# usb_hub.net
KiCad netlist of a schematic drawn in EAGLE
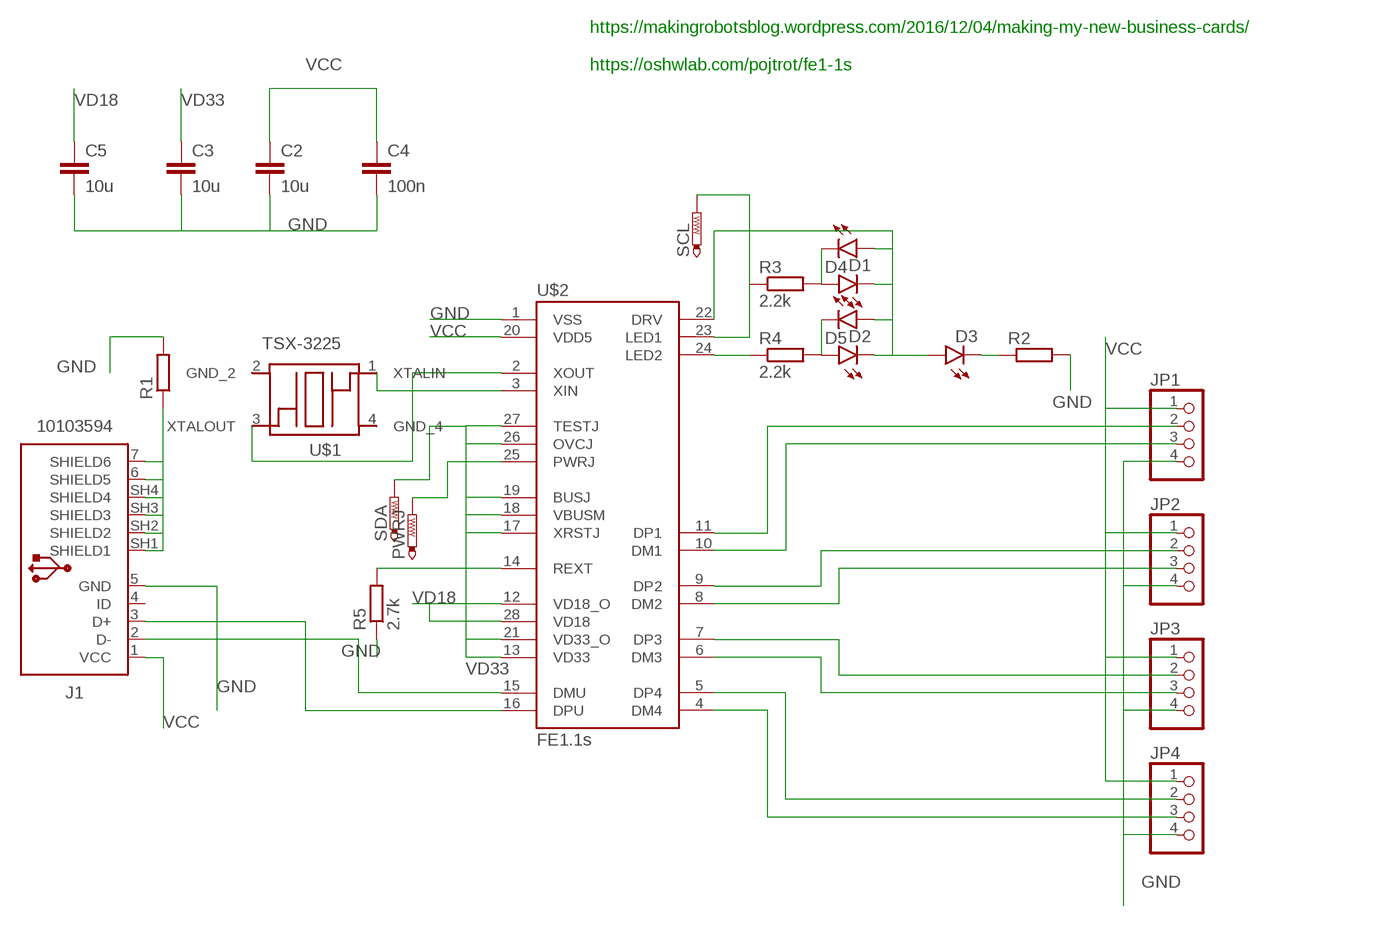
[diagram p0: schematic, sheet 1]

(export (version "E")
  (design (tool "Eeschema 10.0.6"))
  (components
    (comp (ref "C2")
      (value "10u")
      (footprint "eagle-import:C0805")
      (libsource (lib "eagle-import") (part "C-EUC0805"))
    )
    (comp (ref "C3")
      (value "10u")
      (footprint "eagle-import:C0805")
      (libsource (lib "eagle-import") (part "C-EUC0805"))
    )
    (comp (ref "C4")
      (value "100n")
      (footprint "eagle-import:C0603")
      (libsource (lib "eagle-import") (part "C-EUC0603"))
    )
    (comp (ref "C5")
      (value "10u")
      (footprint "eagle-import:C0805")
      (libsource (lib "eagle-import") (part "C-EUC0805"))
    )
    (comp (ref "D1")
      (value "LEDCHIP-LED0603")
      (footprint "eagle-import:CHIP-LED0603")
      (libsource (lib "eagle-import") (part "LEDCHIP-LED0603"))
    )
    (comp (ref "D2")
      (value "LEDCHIP-LED0603")
      (footprint "eagle-import:CHIP-LED0603")
      (libsource (lib "eagle-import") (part "LEDCHIP-LED0603"))
    )
    (comp (ref "D3")
      (value "LEDCHIP-LED0603")
      (footprint "eagle-import:CHIP-LED0603")
      (libsource (lib "eagle-import") (part "LEDCHIP-LED0603"))
    )
    (comp (ref "D4")
      (value "LEDCHIP-LED0603")
      (footprint "eagle-import:CHIP-LED0603")
      (libsource (lib "eagle-import") (part "LEDCHIP-LED0603"))
    )
    (comp (ref "D5")
      (value "LEDCHIP-LED0603")
      (footprint "eagle-import:CHIP-LED0603")
      (libsource (lib "eagle-import") (part "LEDCHIP-LED0603"))
    )
    (comp (ref "J1")
      (value "10103594")
      (footprint "eagle-import:10103594")
      (fields (field (name "MANUFACTURER") "Amphenol ICC (FCI)") (field (name "MPN") "10103594-0001LF"))
      (libsource (lib "eagle-import") (part "10103594"))
    )
    (comp (ref "JP1")
      (value "PINHD-1X4")
      (footprint "eagle-import:1X04")
      (libsource (lib "eagle-import") (part "PINHD-1X4"))
    )
    (comp (ref "JP2")
      (value "PINHD-1X4")
      (footprint "eagle-import:1X04")
      (libsource (lib "eagle-import") (part "PINHD-1X4"))
    )
    (comp (ref "JP3")
      (value "PINHD-1X4")
      (footprint "eagle-import:1X04")
      (libsource (lib "eagle-import") (part "PINHD-1X4"))
    )
    (comp (ref "JP4")
      (value "PINHD-1X4")
      (footprint "eagle-import:1X04")
      (libsource (lib "eagle-import") (part "PINHD-1X4"))
    )
    (comp (ref "PWRJ")
      (value "PTR1B1,27")
      (footprint "eagle-import:B1,27")
      (libsource (lib "eagle-import") (part "PTR1B1,27"))
    )
    (comp (ref "R1")
      (value "R-EU_R0603")
      (footprint "eagle-import:R0603")
      (libsource (lib "eagle-import") (part "R-EU_R0603"))
    )
    (comp (ref "R2")
      (value "R-EU_R0603")
      (footprint "eagle-import:R0603")
      (libsource (lib "eagle-import") (part "R-EU_R0603"))
    )
    (comp (ref "R3")
      (value "2.2k")
      (footprint "eagle-import:R0603")
      (libsource (lib "eagle-import") (part "R-EU_R0603"))
    )
    (comp (ref "R4")
      (value "2.2k")
      (footprint "eagle-import:R0603")
      (libsource (lib "eagle-import") (part "R-EU_R0603"))
    )
    (comp (ref "R5")
      (value "2.7k")
      (footprint "eagle-import:R0603")
      (libsource (lib "eagle-import") (part "R-EU_R0603"))
    )
    (comp (ref "SCL")
      (value "PTR1B1,27")
      (footprint "eagle-import:B1,27")
      (libsource (lib "eagle-import") (part "PTR1B1,27"))
    )
    (comp (ref "SDA")
      (value "PTR1B1,27")
      (footprint "eagle-import:B1,27")
      (libsource (lib "eagle-import") (part "PTR1B1,27"))
    )
    (comp (ref "U$1")
      (value "TSX-3225")
      (footprint "eagle-import:TSX-3225")
      (libsource (lib "eagle-import") (part "TSX-3225"))
    )
    (comp (ref "U$2")
      (value "FE1.1S")
      (footprint "eagle-import:FE1.1S_SSOP-28")
      (libsource (lib "eagle-import") (part "FE1.1S"))
    )
  )
  (nets
    (net (code "1") (name "/GND") (class "Default")
      (node (ref "C2") (pin "2") (pinfunction "2_2") (pintype "passive"))
      (node (ref "C3") (pin "2") (pinfunction "2_2") (pintype "passive"))
      (node (ref "C4") (pin "2") (pinfunction "2_2") (pintype "passive"))
      (node (ref "C5") (pin "2") (pinfunction "2_2") (pintype "passive"))
      (node (ref "J1") (pin "5") (pinfunction "GND_5") (pintype "power_in"))
      (node (ref "JP1") (pin "4") (pinfunction "4_4") (pintype "passive"))
      (node (ref "JP2") (pin "4") (pinfunction "4_4") (pintype "passive"))
      (node (ref "JP3") (pin "4") (pinfunction "4_4") (pintype "passive"))
      (node (ref "JP4") (pin "4") (pinfunction "4_4") (pintype "passive"))
      (node (ref "R1") (pin "2") (pinfunction "2_2") (pintype "passive"))
      (node (ref "R2") (pin "2") (pinfunction "2_2") (pintype "passive"))
      (node (ref "R5") (pin "1") (pinfunction "1_1") (pintype "passive"))
      (node (ref "U$2") (pin "1") (pinfunction "VSS_1") (pintype "bidirectional"))
    )
    (net (code "2") (name "/VCC") (class "Default")
      (node (ref "C2") (pin "1") (pinfunction "1_1") (pintype "passive"))
      (node (ref "C4") (pin "1") (pinfunction "1_1") (pintype "passive"))
      (node (ref "J1") (pin "1") (pinfunction "VCC_1") (pintype "power_in"))
      (node (ref "JP1") (pin "1") (pinfunction "1_1") (pintype "passive"))
      (node (ref "JP2") (pin "1") (pinfunction "1_1") (pintype "passive"))
      (node (ref "JP3") (pin "1") (pinfunction "1_1") (pintype "passive"))
      (node (ref "JP4") (pin "1") (pinfunction "1_1") (pintype "passive"))
      (node (ref "U$2") (pin "20") (pinfunction "VDD5_20") (pintype "bidirectional"))
    )
    (net (code "3") (name "/VD18") (class "Default")
      (node (ref "C5") (pin "1") (pinfunction "1_1") (pintype "passive"))
      (node (ref "U$2") (pin "12") (pinfunction "VD18_O_12") (pintype "bidirectional"))
      (node (ref "U$2") (pin "28") (pinfunction "VD18_28") (pintype "bidirectional"))
    )
    (net (code "4") (name "/VD33") (class "Default")
      (node (ref "C3") (pin "1") (pinfunction "1_1") (pintype "passive"))
      (node (ref "SDA") (pin "TP") (pinfunction "TP_TP") (pintype "input"))
      (node (ref "U$2") (pin "13") (pinfunction "VD33_13") (pintype "bidirectional"))
      (node (ref "U$2") (pin "17") (pinfunction "XRSTJ_17") (pintype "bidirectional"))
      (node (ref "U$2") (pin "18") (pinfunction "VBUSM_18") (pintype "bidirectional"))
      (node (ref "U$2") (pin "19") (pinfunction "BUSJ_19") (pintype "bidirectional"))
      (node (ref "U$2") (pin "21") (pinfunction "VD33_O_21") (pintype "bidirectional"))
      (node (ref "U$2") (pin "26") (pinfunction "OVCJ_26") (pintype "bidirectional"))
      (node (ref "U$2") (pin "27") (pinfunction "TESTJ_27") (pintype "bidirectional"))
    )
    (net (code "5") (name "Net-(D1-PadA)") (class "Default")
      (node (ref "D1") (pin "A") (pinfunction "A_A") (pintype "passive"))
      (node (ref "D4") (pin "C") (pinfunction "C_C") (pintype "passive"))
      (node (ref "R3") (pin "2") (pinfunction "2_2") (pintype "passive"))
    )
    (net (code "6") (name "Net-(D2-PadA)") (class "Default")
      (node (ref "D2") (pin "A") (pinfunction "A_A") (pintype "passive"))
      (node (ref "D5") (pin "C") (pinfunction "C_C") (pintype "passive"))
      (node (ref "R4") (pin "2") (pinfunction "2_2") (pintype "passive"))
    )
    (net (code "7") (name "Net-(D3-PadC)") (class "Default")
      (node (ref "D3") (pin "C") (pinfunction "C_C") (pintype "passive"))
      (node (ref "R2") (pin "1") (pinfunction "1_1") (pintype "passive"))
    )
    (net (code "8") (name "Net-(J1-D+)") (class "Default")
      (node (ref "J1") (pin "3") (pinfunction "D+_3") (pintype "bidirectional"))
      (node (ref "U$2") (pin "16") (pinfunction "DPU_16") (pintype "bidirectional"))
    )
    (net (code "9") (name "Net-(J1-D-)") (class "Default")
      (node (ref "J1") (pin "2") (pinfunction "D-_2") (pintype "bidirectional"))
      (node (ref "U$2") (pin "15") (pinfunction "DMU_15") (pintype "bidirectional"))
    )
    (net (code "10") (name "Net-(J1-SHIELD1)") (class "Default")
      (node (ref "J1") (pin "6") (pinfunction "SHIELD5_6") (pintype "power_in"))
      (node (ref "J1") (pin "7") (pinfunction "SHIELD6_7") (pintype "power_in"))
      (node (ref "J1") (pin "SH1") (pinfunction "SHIELD1_SH1") (pintype "power_in"))
      (node (ref "J1") (pin "SH2") (pinfunction "SHIELD2_SH2") (pintype "power_in"))
      (node (ref "J1") (pin "SH3") (pinfunction "SHIELD3_SH3") (pintype "power_in"))
      (node (ref "J1") (pin "SH4") (pinfunction "SHIELD4_SH4") (pintype "power_in"))
      (node (ref "R1") (pin "1") (pinfunction "1_1") (pintype "passive"))
    )
    (net (code "11") (name "Net-(U$1-XTALIN)") (class "Default")
      (node (ref "U$1") (pin "1") (pinfunction "XTALIN_1") (pintype "bidirectional"))
      (node (ref "U$2") (pin "3") (pinfunction "XIN_3") (pintype "bidirectional"))
    )
    (net (code "12") (name "Net-(U$1-XTALOUT)") (class "Default")
      (node (ref "U$1") (pin "3") (pinfunction "XTALOUT_3") (pintype "bidirectional"))
      (node (ref "U$2") (pin "2") (pinfunction "XOUT_2") (pintype "bidirectional"))
    )
    (net (code "13") (name "Net-(U$2-DM1)") (class "Default")
      (node (ref "JP1") (pin "3") (pinfunction "3_3") (pintype "passive"))
      (node (ref "U$2") (pin "10") (pinfunction "DM1_10") (pintype "bidirectional"))
    )
    (net (code "14") (name "Net-(U$2-DM2)") (class "Default")
      (node (ref "JP2") (pin "3") (pinfunction "3_3") (pintype "passive"))
      (node (ref "U$2") (pin "8") (pinfunction "DM2_8") (pintype "bidirectional"))
    )
    (net (code "15") (name "Net-(U$2-DM3)") (class "Default")
      (node (ref "JP3") (pin "3") (pinfunction "3_3") (pintype "passive"))
      (node (ref "U$2") (pin "6") (pinfunction "DM3_6") (pintype "bidirectional"))
    )
    (net (code "16") (name "Net-(U$2-DM4)") (class "Default")
      (node (ref "JP4") (pin "3") (pinfunction "3_3") (pintype "passive"))
      (node (ref "U$2") (pin "4") (pinfunction "DM4_4") (pintype "bidirectional"))
    )
    (net (code "17") (name "Net-(U$2-DP1)") (class "Default")
      (node (ref "JP1") (pin "2") (pinfunction "2_2") (pintype "passive"))
      (node (ref "U$2") (pin "11") (pinfunction "DP1_11") (pintype "bidirectional"))
    )
    (net (code "18") (name "Net-(U$2-DP2)") (class "Default")
      (node (ref "JP2") (pin "2") (pinfunction "2_2") (pintype "passive"))
      (node (ref "U$2") (pin "9") (pinfunction "DP2_9") (pintype "bidirectional"))
    )
    (net (code "19") (name "Net-(U$2-DP3)") (class "Default")
      (node (ref "JP3") (pin "2") (pinfunction "2_2") (pintype "passive"))
      (node (ref "U$2") (pin "7") (pinfunction "DP3_7") (pintype "bidirectional"))
    )
    (net (code "20") (name "Net-(U$2-DP4)") (class "Default")
      (node (ref "JP4") (pin "2") (pinfunction "2_2") (pintype "passive"))
      (node (ref "U$2") (pin "5") (pinfunction "DP4_5") (pintype "bidirectional"))
    )
    (net (code "21") (name "Net-(U$2-DRV)") (class "Default")
      (node (ref "D1") (pin "C") (pinfunction "C_C") (pintype "passive"))
      (node (ref "D2") (pin "C") (pinfunction "C_C") (pintype "passive"))
      (node (ref "D3") (pin "A") (pinfunction "A_A") (pintype "passive"))
      (node (ref "D4") (pin "A") (pinfunction "A_A") (pintype "passive"))
      (node (ref "D5") (pin "A") (pinfunction "A_A") (pintype "passive"))
      (node (ref "U$2") (pin "22") (pinfunction "DRV_22") (pintype "bidirectional"))
    )
    (net (code "22") (name "Net-(U$2-LED1)") (class "Default")
      (node (ref "R3") (pin "1") (pinfunction "1_1") (pintype "passive"))
      (node (ref "SCL") (pin "TP") (pinfunction "TP_TP") (pintype "input"))
      (node (ref "U$2") (pin "23") (pinfunction "LED1_23") (pintype "bidirectional"))
    )
    (net (code "23") (name "Net-(U$2-LED2)") (class "Default")
      (node (ref "R4") (pin "1") (pinfunction "1_1") (pintype "passive"))
      (node (ref "U$2") (pin "24") (pinfunction "LED2_24") (pintype "bidirectional"))
    )
    (net (code "24") (name "Net-(U$2-PWRJ)") (class "Default")
      (node (ref "PWRJ") (pin "TP") (pinfunction "TP_TP") (pintype "input"))
      (node (ref "U$2") (pin "25") (pinfunction "PWRJ_25") (pintype "bidirectional"))
    )
    (net (code "25") (name "Net-(U$2-REXT)") (class "Default")
      (node (ref "R5") (pin "2") (pinfunction "2_2") (pintype "passive"))
      (node (ref "U$2") (pin "14") (pinfunction "REXT_14") (pintype "bidirectional"))
    )
    (net (code "26") (name "unconnected-(J1-ID-Pad4)") (class "Default")
      (node (ref "J1") (pin "4") (pinfunction "ID_4") (pintype "bidirectional"))
    )
    (net (code "27") (name "unconnected-(U$1-GND_2-Pad2)") (class "Default")
      (node (ref "U$1") (pin "2") (pinfunction "GND_2_2") (pintype "bidirectional"))
    )
    (net (code "28") (name "unconnected-(U$1-GND_4-Pad4)") (class "Default")
      (node (ref "U$1") (pin "4") (pinfunction "GND_4_4") (pintype "bidirectional"))
    )
  )
)
